# ST25D.net
KiCad netlist of a schematic drawn in Altium Designer
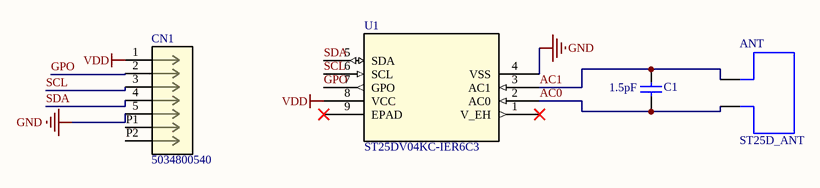
[diagram p0: ST25D.SchDoc]

(export (version "E")
  (design (tool "Eeschema 10.0.6"))
  (components
    (comp (ref "ANT")
      (value "ST25D_ANT")
      (footprint "ESL_NFC_ANT")
      (description "ST25D antenna")
      (libsource (lib "missing_parts") (part "ST25D_ANT"))
    )
    (comp (ref "C1")
      (value "1.5pF")
      (footprint "C0402")
      (description "Multilayer Ceramic Capacitor, 1.5 pF, 50 V, ± 0.1pF, C0G (NP0), 0402 [1005 Metric]")
      (fields
        (field (name "MANUFACTURER") "Murata")
        (field (name "MANUFACTURER PART NUMBER") "GJM1555C1H1R5BB01D")
      )
      (libsource (lib "MCD_PARTS_database") (part "Capacitor"))
    )
    (comp (ref "CN1")
      (value "5034800540")
      (footprint "CON_5034800540_MOL")
      (fields
        (field (name "MANUFACTURER") "Molex Connector Corporation")
        (field (name "COPYRIGHT") "Copyright (C) 2023 Ultra Librarian. All rights reserved.")
      )
      (libsource (lib "missing_parts") (part "5034800540_5_circuits"))
    )
    (comp (ref "U1")
      (value "ST25DV04KC-IER6C3")
      (footprint "UFDFPN8_STM")
      (description "NFC/RFID Tag and Transponder IC 13553kHz to 13567kHz 4Kbit 8-Pin UFDFPN T/R")
      (fields
        (field (name "MANUFACTURER_PART_NUMBER") "ST25DV04K-IER6C3")
        (field (name "MANUFACTURER") "STMicroelectronics")
        (field (name "COPYRIGHT") "Copyright (C) 2023 Ultra Librarian. All rights reserved.")
      )
      (libsource (lib "missing_parts") (part "ST25DV04K-IER6C3"))
    )
  )
  (nets
    (net (code "1") (name "/AC0") (class "Default")
      (node (ref "ANT") (pin "2") (pinfunction "2_2") (pintype "passive"))
      (node (ref "C1") (pin "2") (pinfunction "2_2") (pintype "passive"))
      (node (ref "U1") (pin "2") (pinfunction "AC0_2") (pintype "input"))
    )
    (net (code "2") (name "/AC1") (class "Default")
      (node (ref "ANT") (pin "1") (pinfunction "1_1") (pintype "passive"))
      (node (ref "C1") (pin "1") (pinfunction "1_1") (pintype "passive"))
      (node (ref "U1") (pin "3") (pinfunction "AC1_3") (pintype "input"))
    )
    (net (code "3") (name "/GPO") (class "Default")
      (node (ref "CN1") (pin "2") (pinfunction "2_2") (pintype "passive"))
      (node (ref "U1") (pin "7") (pinfunction "GPO_7") (pintype "output"))
    )
    (net (code "4") (name "/SCL") (class "Default")
      (node (ref "CN1") (pin "3") (pinfunction "3_3") (pintype "passive"))
      (node (ref "U1") (pin "6") (pinfunction "SCL_6") (pintype "input"))
    )
    (net (code "5") (name "/SDA") (class "Default")
      (node (ref "CN1") (pin "4") (pinfunction "4_4") (pintype "passive"))
      (node (ref "U1") (pin "5") (pinfunction "SDA_5") (pintype "bidirectional"))
    )
    (net (code "6") (name "GND") (class "Default")
      (node (ref "CN1") (pin "5") (pinfunction "5_5") (pintype "passive"))
      (node (ref "U1") (pin "4") (pinfunction "VSS_4") (pintype "power_in"))
    )
    (net (code "7") (name "VDD") (class "Default")
      (node (ref "CN1") (pin "1") (pinfunction "1_1") (pintype "passive"))
      (node (ref "U1") (pin "8") (pinfunction "VCC_8") (pintype "power_in"))
    )
    (net (code "8") (name "unconnected-(CN1-PadP1)") (class "Default")
      (node (ref "CN1") (pin "P1") (pinfunction "P1_P1") (pintype "passive"))
    )
    (net (code "9") (name "unconnected-(CN1-PadP2)") (class "Default")
      (node (ref "CN1") (pin "P2") (pinfunction "P2_P2") (pintype "passive"))
    )
    (net (code "10") (name "unconnected-(U1-EPAD-Pad9)") (class "Default")
      (node (ref "U1") (pin "9") (pinfunction "EPAD_9") (pintype "power_in+no_connect"))
    )
    (net (code "11") (name "unconnected-(U1-V_EH-Pad1)") (class "Default")
      (node (ref "U1") (pin "1") (pinfunction "V_EH_1") (pintype "output+no_connect"))
    )
  )
)
